# 7Seg.net
KiCad netlist of a schematic drawn in Altium Designer
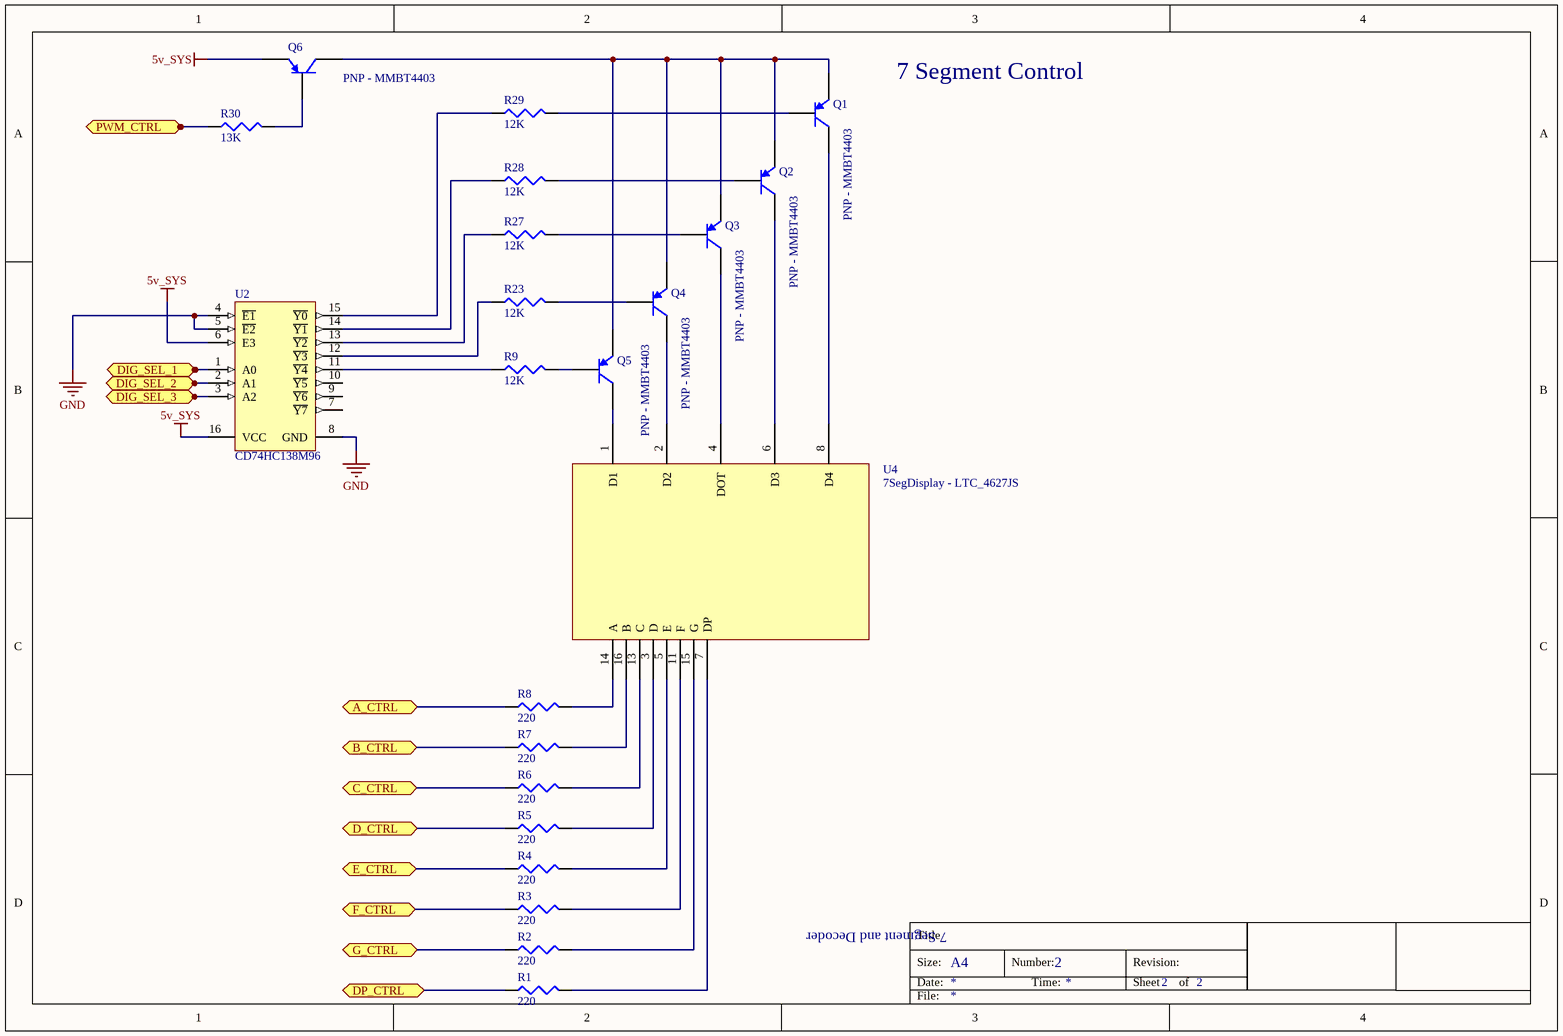
[diagram p0: 7Seg.SchDoc]

(export (version "E")
  (design (tool "Eeschema 10.0.6"))
  (components
    (comp (ref "Q1")
      (value "PNP - MMBT4403")
      (footprint "TO-92A - BJT")
      (description "PNP Bipolar Transistor")
      (libsource (lib "lab2") (part "PNP - MMBT4403"))
    )
    (comp (ref "Q2")
      (value "PNP - MMBT4403")
      (footprint "TO-92A - BJT")
      (description "PNP Bipolar Transistor")
      (libsource (lib "lab2") (part "PNP - MMBT4403"))
    )
    (comp (ref "Q3")
      (value "PNP - MMBT4403")
      (footprint "TO-92A - BJT")
      (description "PNP Bipolar Transistor")
      (libsource (lib "lab2") (part "PNP - MMBT4403"))
    )
    (comp (ref "Q4")
      (value "PNP - MMBT4403")
      (footprint "TO-92A - BJT")
      (description "PNP Bipolar Transistor")
      (libsource (lib "lab2") (part "PNP - MMBT4403"))
    )
    (comp (ref "Q5")
      (value "PNP - MMBT4403")
      (footprint "TO-92A - BJT")
      (description "PNP Bipolar Transistor")
      (libsource (lib "lab2") (part "PNP - MMBT4403"))
    )
    (comp (ref "Q6")
      (value "PNP - MMBT4403")
      (footprint "TO-92A - BJT")
      (description "PNP Bipolar Transistor")
      (libsource (lib "lab2") (part "PNP - MMBT4403"))
    )
    (comp (ref "R1")
      (value "220")
      (footprint "J1-0603")
      (description "Resistor")
      (fields (field (name "PUBLISHER") "Altium Limited"))
      (libsource (lib "lab2") (part "Res3"))
    )
    (comp (ref "R2")
      (value "220")
      (footprint "J1-0603")
      (description "Resistor")
      (fields (field (name "PUBLISHER") "Altium Limited"))
      (libsource (lib "lab2") (part "Res3"))
    )
    (comp (ref "R3")
      (value "220")
      (footprint "J1-0603")
      (description "Resistor")
      (fields (field (name "PUBLISHER") "Altium Limited"))
      (libsource (lib "lab2") (part "Res3"))
    )
    (comp (ref "R4")
      (value "220")
      (footprint "J1-0603")
      (description "Resistor")
      (fields (field (name "PUBLISHER") "Altium Limited"))
      (libsource (lib "lab2") (part "Res3"))
    )
    (comp (ref "R5")
      (value "220")
      (footprint "J1-0603")
      (description "Resistor")
      (fields (field (name "PUBLISHER") "Altium Limited"))
      (libsource (lib "lab2") (part "Res3"))
    )
    (comp (ref "R6")
      (value "220")
      (footprint "J1-0603")
      (description "Resistor")
      (fields (field (name "PUBLISHER") "Altium Limited"))
      (libsource (lib "lab2") (part "Res3"))
    )
    (comp (ref "R7")
      (value "220")
      (footprint "J1-0603")
      (description "Resistor")
      (fields (field (name "PUBLISHER") "Altium Limited"))
      (libsource (lib "lab2") (part "Res3"))
    )
    (comp (ref "R8")
      (value "220")
      (footprint "J1-0603")
      (description "Resistor")
      (fields (field (name "PUBLISHER") "Altium Limited"))
      (libsource (lib "lab2") (part "Res3"))
    )
    (comp (ref "R9")
      (value "12K")
      (footprint "J1-0603")
      (description "Resistor")
      (fields (field (name "PUBLISHER") "Altium Limited"))
      (libsource (lib "lab2") (part "Res3"))
    )
    (comp (ref "R23")
      (value "12K")
      (footprint "J1-0603")
      (description "Resistor")
      (fields (field (name "PUBLISHER") "Altium Limited"))
      (libsource (lib "lab2") (part "Res3"))
    )
    (comp (ref "R27")
      (value "12K")
      (footprint "J1-0603")
      (description "Resistor")
      (fields (field (name "PUBLISHER") "Altium Limited"))
      (libsource (lib "lab2") (part "Res3"))
    )
    (comp (ref "R28")
      (value "12K")
      (footprint "J1-0603")
      (description "Resistor")
      (fields (field (name "PUBLISHER") "Altium Limited"))
      (libsource (lib "lab2") (part "Res3"))
    )
    (comp (ref "R29")
      (value "12K")
      (footprint "J1-0603")
      (description "Resistor")
      (fields (field (name "PUBLISHER") "Altium Limited"))
      (libsource (lib "lab2") (part "Res3"))
    )
    (comp (ref "R30")
      (value "13K")
      (footprint "J1-0603")
      (description "Resistor")
      (fields (field (name "PUBLISHER") "Altium Limited"))
      (libsource (lib "lab2") (part "Res3"))
    )
    (comp (ref "U2")
      (value "CD74HC138M96")
      (footprint "D0016A_L")
      (fields
        (field (name "GENERIC PART NUMBER") "CD74HC138")
        (field (name "MANUFACTURER") "Texas Instruments")
      )
      (libsource (lib "Altium Content Vault") (part "TI-CDX4HCT138-16"))
    )
    (comp (ref "U4") (value "7SegDisplay - LTC_4627JS") (libsource (lib "lab2") (part "7SegDisplay")))
  )
  (nets
    (net (code "1") (name "/A_CTRL") (class "Default")
      (node (ref "R8") (pin "1") (pinfunction "1_1") (pintype "passive"))
    )
    (net (code "2") (name "/B_CTRL") (class "Default")
      (node (ref "R7") (pin "1") (pinfunction "1_1") (pintype "passive"))
    )
    (net (code "3") (name "/C_CTRL") (class "Default")
      (node (ref "R6") (pin "1") (pinfunction "1_1") (pintype "passive"))
    )
    (net (code "4") (name "/DIG_SEL_1") (class "Default")
      (node (ref "U2") (pin "1") (pinfunction "A0_1") (pintype "input"))
    )
    (net (code "5") (name "/DIG_SEL_2") (class "Default")
      (node (ref "U2") (pin "2") (pinfunction "A1_2") (pintype "input"))
    )
    (net (code "6") (name "/DIG_SEL_3") (class "Default")
      (node (ref "U2") (pin "3") (pinfunction "A2_3") (pintype "input"))
    )
    (net (code "7") (name "/DP_CTRL") (class "Default")
      (node (ref "R1") (pin "1") (pinfunction "1_1") (pintype "passive"))
    )
    (net (code "8") (name "/D_CTRL") (class "Default")
      (node (ref "R5") (pin "1") (pinfunction "1_1") (pintype "passive"))
    )
    (net (code "9") (name "/E_CTRL") (class "Default")
      (node (ref "R4") (pin "1") (pinfunction "1_1") (pintype "passive"))
    )
    (net (code "10") (name "/F_CTRL") (class "Default")
      (node (ref "R3") (pin "1") (pinfunction "1_1") (pintype "passive"))
    )
    (net (code "11") (name "/G_CTRL") (class "Default")
      (node (ref "R2") (pin "1") (pinfunction "1_1") (pintype "passive"))
    )
    (net (code "12") (name "/PWM_CTRL") (class "Default")
      (node (ref "R30") (pin "1") (pinfunction "1_1") (pintype "passive"))
    )
    (net (code "13") (name "5v_SYS") (class "Default")
      (node (ref "Q6") (pin "3") (pinfunction "E_3") (pintype "passive"))
      (node (ref "U2") (pin "16") (pinfunction "VCC_16") (pintype "power_in"))
      (node (ref "U2") (pin "6") (pinfunction "E3_6") (pintype "input"))
    )
    (net (code "14") (name "GND") (class "Default")
      (node (ref "U2") (pin "4") (pinfunction "~{E1}_4") (pintype "input"))
      (node (ref "U2") (pin "5") (pinfunction "~{E2}_5") (pintype "input"))
      (node (ref "U2") (pin "8") (pinfunction "GND_8") (pintype "power_in"))
    )
    (net (code "15") (name "Net-(Q1-B)") (class "Default")
      (node (ref "Q1") (pin "2") (pinfunction "B_2") (pintype "passive"))
      (node (ref "R29") (pin "2") (pinfunction "2_2") (pintype "passive"))
    )
    (net (code "16") (name "Net-(Q1-C)") (class "Default")
      (node (ref "Q1") (pin "1") (pinfunction "C_1") (pintype "passive"))
      (node (ref "U4") (pin "8") (pinfunction "D4_8") (pintype "passive"))
    )
    (net (code "17") (name "Net-(Q1-E)") (class "Default")
      (node (ref "Q1") (pin "3") (pinfunction "E_3") (pintype "passive"))
      (node (ref "Q2") (pin "3") (pinfunction "E_3") (pintype "passive"))
      (node (ref "Q3") (pin "3") (pinfunction "E_3") (pintype "passive"))
      (node (ref "Q4") (pin "3") (pinfunction "E_3") (pintype "passive"))
      (node (ref "Q5") (pin "3") (pinfunction "E_3") (pintype "passive"))
      (node (ref "Q6") (pin "1") (pinfunction "C_1") (pintype "passive"))
    )
    (net (code "18") (name "Net-(Q2-B)") (class "Default")
      (node (ref "Q2") (pin "2") (pinfunction "B_2") (pintype "passive"))
      (node (ref "R28") (pin "2") (pinfunction "2_2") (pintype "passive"))
    )
    (net (code "19") (name "Net-(Q2-C)") (class "Default")
      (node (ref "Q2") (pin "1") (pinfunction "C_1") (pintype "passive"))
      (node (ref "U4") (pin "6") (pinfunction "D3_6") (pintype "passive"))
    )
    (net (code "20") (name "Net-(Q3-B)") (class "Default")
      (node (ref "Q3") (pin "2") (pinfunction "B_2") (pintype "passive"))
      (node (ref "R27") (pin "2") (pinfunction "2_2") (pintype "passive"))
    )
    (net (code "21") (name "Net-(Q3-C)") (class "Default")
      (node (ref "Q3") (pin "1") (pinfunction "C_1") (pintype "passive"))
      (node (ref "U4") (pin "4") (pinfunction "DOT_4") (pintype "passive"))
    )
    (net (code "22") (name "Net-(Q4-B)") (class "Default")
      (node (ref "Q4") (pin "2") (pinfunction "B_2") (pintype "passive"))
      (node (ref "R23") (pin "2") (pinfunction "2_2") (pintype "passive"))
    )
    (net (code "23") (name "Net-(Q4-C)") (class "Default")
      (node (ref "Q4") (pin "1") (pinfunction "C_1") (pintype "passive"))
      (node (ref "U4") (pin "2") (pinfunction "D2_2") (pintype "passive"))
    )
    (net (code "24") (name "Net-(Q5-B)") (class "Default")
      (node (ref "Q5") (pin "2") (pinfunction "B_2") (pintype "passive"))
      (node (ref "R9") (pin "2") (pinfunction "2_2") (pintype "passive"))
    )
    (net (code "25") (name "Net-(Q5-C)") (class "Default")
      (node (ref "Q5") (pin "1") (pinfunction "C_1") (pintype "passive"))
      (node (ref "U4") (pin "1") (pinfunction "D1_1") (pintype "passive"))
    )
    (net (code "26") (name "Net-(Q6-B)") (class "Default")
      (node (ref "Q6") (pin "2") (pinfunction "B_2") (pintype "passive"))
      (node (ref "R30") (pin "2") (pinfunction "2_2") (pintype "passive"))
    )
    (net (code "27") (name "Net-(U2-~{Y0})") (class "Default")
      (node (ref "R29") (pin "1") (pinfunction "1_1") (pintype "passive"))
      (node (ref "U2") (pin "15") (pinfunction "~{Y0}_15") (pintype "output"))
    )
    (net (code "28") (name "Net-(U2-~{Y1})") (class "Default")
      (node (ref "R28") (pin "1") (pinfunction "1_1") (pintype "passive"))
      (node (ref "U2") (pin "14") (pinfunction "~{Y1}_14") (pintype "output"))
    )
    (net (code "29") (name "Net-(U2-~{Y2})") (class "Default")
      (node (ref "R27") (pin "1") (pinfunction "1_1") (pintype "passive"))
      (node (ref "U2") (pin "13") (pinfunction "~{Y2}_13") (pintype "output"))
    )
    (net (code "30") (name "Net-(U2-~{Y3})") (class "Default")
      (node (ref "R23") (pin "1") (pinfunction "1_1") (pintype "passive"))
      (node (ref "U2") (pin "12") (pinfunction "~{Y3}_12") (pintype "output"))
    )
    (net (code "31") (name "Net-(U2-~{Y4})") (class "Default")
      (node (ref "R9") (pin "1") (pinfunction "1_1") (pintype "passive"))
      (node (ref "U2") (pin "11") (pinfunction "~{Y4}_11") (pintype "output"))
    )
    (net (code "32") (name "Net-(U4-A)") (class "Default")
      (node (ref "R8") (pin "2") (pinfunction "2_2") (pintype "passive"))
      (node (ref "U4") (pin "14") (pinfunction "A_14") (pintype "passive"))
    )
    (net (code "33") (name "Net-(U4-B)") (class "Default")
      (node (ref "R7") (pin "2") (pinfunction "2_2") (pintype "passive"))
      (node (ref "U4") (pin "16") (pinfunction "B_16") (pintype "passive"))
    )
    (net (code "34") (name "Net-(U4-C)") (class "Default")
      (node (ref "R6") (pin "2") (pinfunction "2_2") (pintype "passive"))
      (node (ref "U4") (pin "13") (pinfunction "C_13") (pintype "passive"))
    )
    (net (code "35") (name "Net-(U4-D)") (class "Default")
      (node (ref "R5") (pin "2") (pinfunction "2_2") (pintype "passive"))
      (node (ref "U4") (pin "3") (pinfunction "D_3") (pintype "passive"))
    )
    (net (code "36") (name "Net-(U4-DP)") (class "Default")
      (node (ref "R1") (pin "2") (pinfunction "2_2") (pintype "passive"))
      (node (ref "U4") (pin "7") (pinfunction "DP_7") (pintype "passive"))
    )
    (net (code "37") (name "Net-(U4-E)") (class "Default")
      (node (ref "R4") (pin "2") (pinfunction "2_2") (pintype "passive"))
      (node (ref "U4") (pin "5") (pinfunction "E_5") (pintype "passive"))
    )
    (net (code "38") (name "Net-(U4-F)") (class "Default")
      (node (ref "R3") (pin "2") (pinfunction "2_2") (pintype "passive"))
      (node (ref "U4") (pin "11") (pinfunction "F_11") (pintype "passive"))
    )
    (net (code "39") (name "Net-(U4-G)") (class "Default")
      (node (ref "R2") (pin "2") (pinfunction "2_2") (pintype "passive"))
      (node (ref "U4") (pin "15") (pinfunction "G_15") (pintype "passive"))
    )
    (net (code "40") (name "unconnected-(U2-~{Y5}-Pad10)") (class "Default")
      (node (ref "U2") (pin "10") (pinfunction "~{Y5}_10") (pintype "output"))
    )
    (net (code "41") (name "unconnected-(U2-~{Y6}-Pad9)") (class "Default")
      (node (ref "U2") (pin "9") (pinfunction "~{Y6}_9") (pintype "output"))
    )
    (net (code "42") (name "unconnected-(U2-~{Y7}-Pad7)") (class "Default")
      (node (ref "U2") (pin "7") (pinfunction "~{Y7}_7") (pintype "output"))
    )
  )
)
